# ESP32-S3.net
KiCad netlist of a schematic drawn in Altium Designer
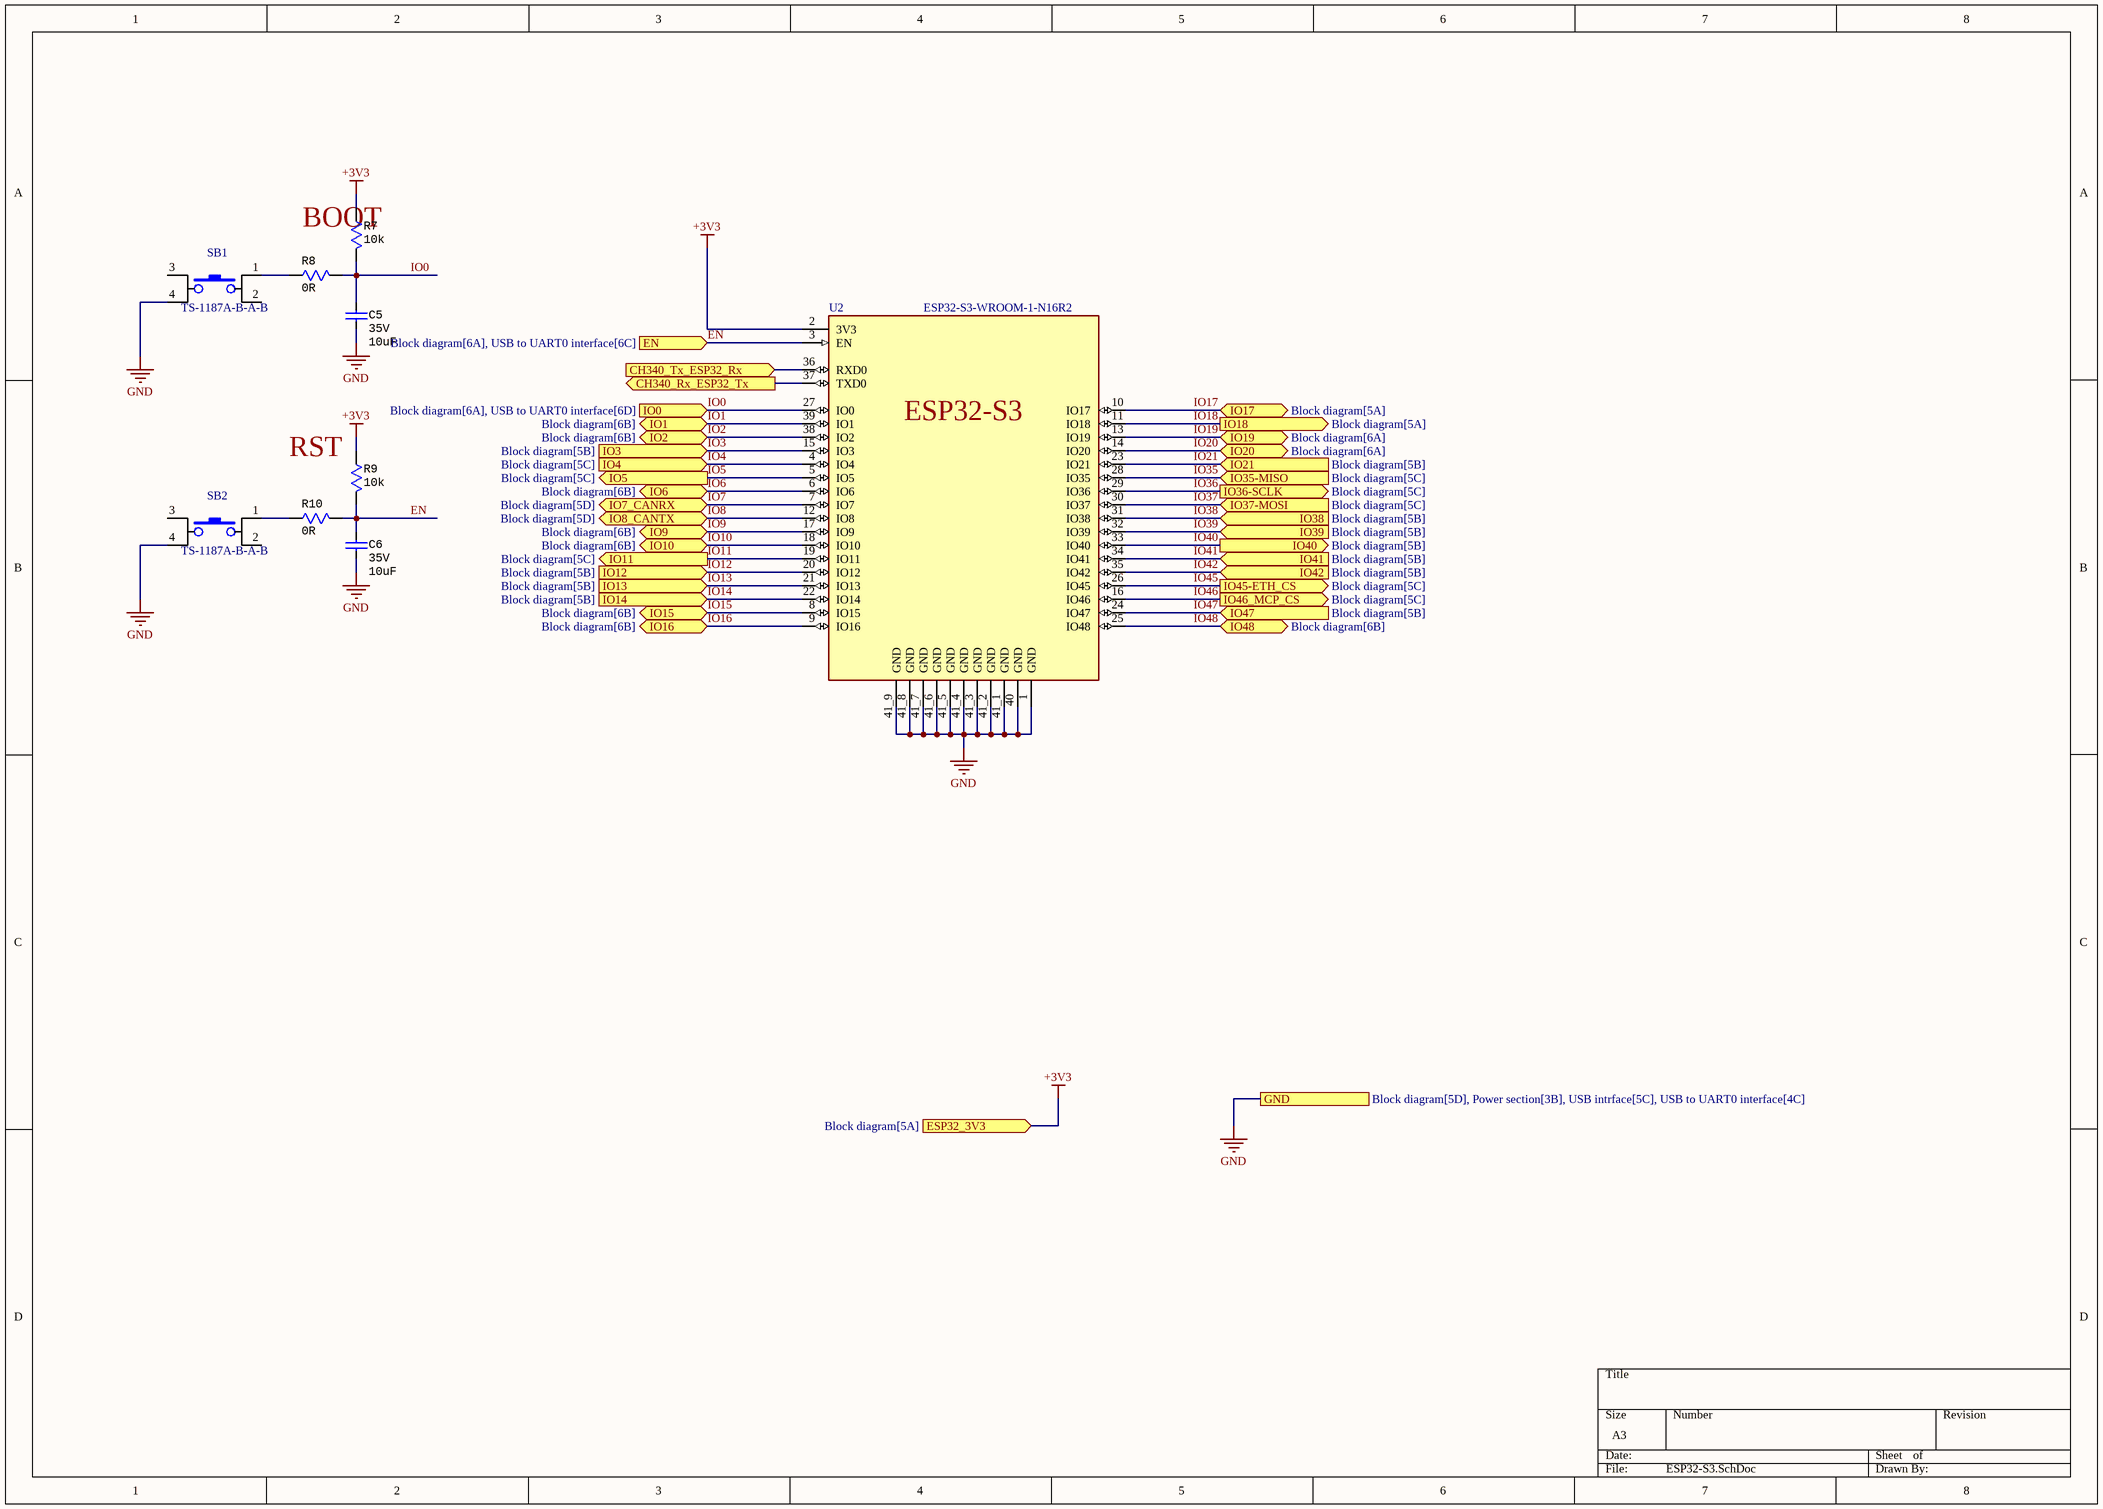
[diagram p0: ESP32-S3.SchDoc]

(export (version "E")
  (design (tool "Eeschema 10.0.6"))
  (components
    (comp (ref "C5")
      (value "10uF")
      (footprint "CAP Ceramic SMD 0603")
      (description "Cap Ceramic 10uF 35V X5R 20% Pad SMD 0603 85C T/R")
      (fields
        (field (name "MANUFACTURER") "Murata")
        (field (name "MANUFACTURER PART NUMBER") "GRM188R6YA106MA73D")
        (field (name "VOLTAGE") "35V")
      )
      (libsource (lib "Passive") (part "CAP 0603 10uF 35V"))
    )
    (comp (ref "C6")
      (value "10uF")
      (footprint "CAP Ceramic SMD 0603")
      (description "Cap Ceramic 10uF 35V X5R 20% Pad SMD 0603 85C T/R")
      (fields
        (field (name "MANUFACTURER") "Murata")
        (field (name "MANUFACTURER PART NUMBER") "GRM188R6YA106MA73D")
        (field (name "VOLTAGE") "35V")
      )
      (libsource (lib "Passive") (part "CAP 0603 10uF 35V"))
    )
    (comp (ref "R7")
      (value "10k")
      (footprint "RES SMD 0603")
      (description "Res Thick Film 0603 10K Ohm 1% 1/10W ±100ppm/°C Molded SMD Punched Carrier T/R")
      (fields
        (field (name "MANUFACTURER") "Panasonic")
        (field (name "MANUFACTURER PART NUMBER") "ERJ-3EKF1002V")
      )
      (libsource (lib "Passive") (part "RES 0603 10k 1%"))
    )
    (comp (ref "R8")
      (value "0R")
      (footprint "RES SMD 0603")
      (description "ERJ Series 0603 0 Ohm 0.05 W Jumper Surface Mount Thick Film Chip Resistor")
      (fields (field (name "TOLERANCE") "1%") (field (name "MANUFACTURER") "Panasonic"))
      (libsource (lib "Passive") (part "RES 0603 0R 1%"))
    )
    (comp (ref "R9")
      (value "10k")
      (footprint "RES SMD 0603")
      (description "Res Thick Film 0603 10K Ohm 1% 1/10W ±100ppm/°C Molded SMD Punched Carrier T/R")
      (fields
        (field (name "MANUFACTURER") "Panasonic")
        (field (name "MANUFACTURER PART NUMBER") "ERJ-3EKF1002V")
      )
      (libsource (lib "Passive") (part "RES 0603 10k 1%"))
    )
    (comp (ref "R10")
      (value "0R")
      (footprint "RES SMD 0603")
      (description "ERJ Series 0603 0 Ohm 0.05 W Jumper Surface Mount Thick Film Chip Resistor")
      (fields (field (name "TOLERANCE") "1%") (field (name "MANUFACTURER") "Panasonic"))
      (libsource (lib "Passive") (part "RES 0603 0R 1%"))
    )
    (comp (ref "SB1")
      (value "TS-1187A-B-A-B")
      (footprint "SW-SMD-4X4X1.5")
      (libsource (lib "Switches") (part "TS-1187A-B-A-B"))
    )
    (comp (ref "SB2")
      (value "TS-1187A-B-A-B")
      (footprint "SW-SMD-4X4X1.5")
      (libsource (lib "Switches") (part "TS-1187A-B-A-B"))
    )
    (comp (ref "U2")
      (value "ESP32-S3-WROOM-1-N16R2")
      (footprint "ESP32-S3-WROOM-1-N16R2")
      (description "WiFi-Modul 802.11/BT 2, 4-2, 5GHz 150Mb/s")
      (fields (field (name "MANUFACTURER") "Espressif Systems"))
      (libsource (lib "Miscellaneous MCU") (part "ESP32-S3-WROOM-1-N16R2"))
    )
  )
  (nets
    (net (code "1") (name "+3V3") (class "Default")
      (node (ref "R7") (pin "2") (pinfunction "2_2") (pintype "passive"))
      (node (ref "R9") (pin "2") (pinfunction "2_2") (pintype "passive"))
      (node (ref "U2") (pin "2") (pinfunction "3V3_2") (pintype "power_in"))
    )
    (net (code "2") (name "/CH340_Rx_ESP32_Tx") (class "Default")
      (node (ref "U2") (pin "37") (pinfunction "TXD0_37") (pintype "bidirectional"))
    )
    (net (code "3") (name "/CH340_Tx_ESP32_Rx") (class "Default")
      (node (ref "U2") (pin "36") (pinfunction "RXD0_36") (pintype "bidirectional"))
    )
    (net (code "4") (name "/EN") (class "Default")
      (node (ref "C6") (pin "2") (pinfunction "2_2") (pintype "passive"))
      (node (ref "R10") (pin "1") (pinfunction "1_1") (pintype "passive"))
      (node (ref "R9") (pin "1") (pinfunction "1_1") (pintype "passive"))
      (node (ref "U2") (pin "3") (pinfunction "EN_3") (pintype "input"))
    )
    (net (code "5") (name "/IO0") (class "Default")
      (node (ref "C5") (pin "2") (pinfunction "2_2") (pintype "passive"))
      (node (ref "R7") (pin "1") (pinfunction "1_1") (pintype "passive"))
      (node (ref "R8") (pin "1") (pinfunction "1_1") (pintype "passive"))
      (node (ref "U2") (pin "27") (pinfunction "IO0_27") (pintype "bidirectional"))
    )
    (net (code "6") (name "/IO1") (class "Default")
      (node (ref "U2") (pin "39") (pinfunction "IO1_39") (pintype "bidirectional"))
    )
    (net (code "7") (name "/IO2") (class "Default")
      (node (ref "U2") (pin "38") (pinfunction "IO2_38") (pintype "bidirectional"))
    )
    (net (code "8") (name "/IO3") (class "Default")
      (node (ref "U2") (pin "15") (pinfunction "IO3_15") (pintype "bidirectional"))
    )
    (net (code "9") (name "/IO4") (class "Default")
      (node (ref "U2") (pin "4") (pinfunction "IO4_4") (pintype "bidirectional"))
    )
    (net (code "10") (name "/IO5") (class "Default")
      (node (ref "U2") (pin "5") (pinfunction "IO5_5") (pintype "bidirectional"))
    )
    (net (code "11") (name "/IO6") (class "Default")
      (node (ref "U2") (pin "6") (pinfunction "IO6_6") (pintype "bidirectional"))
    )
    (net (code "12") (name "/IO7") (class "Default")
      (node (ref "U2") (pin "7") (pinfunction "IO7_7") (pintype "bidirectional"))
    )
    (net (code "13") (name "/IO8") (class "Default")
      (node (ref "U2") (pin "12") (pinfunction "IO8_12") (pintype "bidirectional"))
    )
    (net (code "14") (name "/IO9") (class "Default")
      (node (ref "U2") (pin "17") (pinfunction "IO9_17") (pintype "bidirectional"))
    )
    (net (code "15") (name "/IO10") (class "Default")
      (node (ref "U2") (pin "18") (pinfunction "IO10_18") (pintype "bidirectional"))
    )
    (net (code "16") (name "/IO11") (class "Default")
      (node (ref "U2") (pin "19") (pinfunction "IO11_19") (pintype "bidirectional"))
    )
    (net (code "17") (name "/IO12") (class "Default")
      (node (ref "U2") (pin "20") (pinfunction "IO12_20") (pintype "bidirectional"))
    )
    (net (code "18") (name "/IO13") (class "Default")
      (node (ref "U2") (pin "21") (pinfunction "IO13_21") (pintype "bidirectional"))
    )
    (net (code "19") (name "/IO14") (class "Default")
      (node (ref "U2") (pin "22") (pinfunction "IO14_22") (pintype "bidirectional"))
    )
    (net (code "20") (name "/IO15") (class "Default")
      (node (ref "U2") (pin "8") (pinfunction "IO15_8") (pintype "bidirectional"))
    )
    (net (code "21") (name "/IO16") (class "Default")
      (node (ref "U2") (pin "9") (pinfunction "IO16_9") (pintype "bidirectional"))
    )
    (net (code "22") (name "/IO17") (class "Default")
      (node (ref "U2") (pin "10") (pinfunction "IO17_10") (pintype "bidirectional"))
    )
    (net (code "23") (name "/IO18") (class "Default")
      (node (ref "U2") (pin "11") (pinfunction "IO18_11") (pintype "bidirectional"))
    )
    (net (code "24") (name "/IO19") (class "Default")
      (node (ref "U2") (pin "13") (pinfunction "IO19_13") (pintype "bidirectional"))
    )
    (net (code "25") (name "/IO20") (class "Default")
      (node (ref "U2") (pin "14") (pinfunction "IO20_14") (pintype "bidirectional"))
    )
    (net (code "26") (name "/IO21") (class "Default")
      (node (ref "U2") (pin "23") (pinfunction "IO21_23") (pintype "bidirectional"))
    )
    (net (code "27") (name "/IO35") (class "Default")
      (node (ref "U2") (pin "28") (pinfunction "IO35_28") (pintype "bidirectional"))
    )
    (net (code "28") (name "/IO36") (class "Default")
      (node (ref "U2") (pin "29") (pinfunction "IO36_29") (pintype "bidirectional"))
    )
    (net (code "29") (name "/IO37") (class "Default")
      (node (ref "U2") (pin "30") (pinfunction "IO37_30") (pintype "bidirectional"))
    )
    (net (code "30") (name "/IO38") (class "Default")
      (node (ref "U2") (pin "31") (pinfunction "IO38_31") (pintype "bidirectional"))
    )
    (net (code "31") (name "/IO39") (class "Default")
      (node (ref "U2") (pin "32") (pinfunction "IO39_32") (pintype "bidirectional"))
    )
    (net (code "32") (name "/IO40") (class "Default")
      (node (ref "U2") (pin "33") (pinfunction "IO40_33") (pintype "bidirectional"))
    )
    (net (code "33") (name "/IO41") (class "Default")
      (node (ref "U2") (pin "34") (pinfunction "IO41_34") (pintype "bidirectional"))
    )
    (net (code "34") (name "/IO42") (class "Default")
      (node (ref "U2") (pin "35") (pinfunction "IO42_35") (pintype "bidirectional"))
    )
    (net (code "35") (name "/IO45") (class "Default")
      (node (ref "U2") (pin "26") (pinfunction "IO45_26") (pintype "bidirectional"))
    )
    (net (code "36") (name "/IO46") (class "Default")
      (node (ref "U2") (pin "16") (pinfunction "IO46_16") (pintype "bidirectional"))
    )
    (net (code "37") (name "/IO47") (class "Default")
      (node (ref "U2") (pin "24") (pinfunction "IO47_24") (pintype "bidirectional"))
    )
    (net (code "38") (name "/IO48") (class "Default")
      (node (ref "U2") (pin "25") (pinfunction "IO48_25") (pintype "bidirectional"))
    )
    (net (code "39") (name "GND") (class "Default")
      (node (ref "C5") (pin "1") (pinfunction "1_1") (pintype "passive"))
      (node (ref "C6") (pin "1") (pinfunction "1_1") (pintype "passive"))
      (node (ref "SB1") (pin "4") (pinfunction "4_4") (pintype "passive"))
      (node (ref "SB2") (pin "4") (pinfunction "4_4") (pintype "passive"))
      (node (ref "U2") (pin "1") (pinfunction "GND_1") (pintype "power_in"))
      (node (ref "U2") (pin "40") (pinfunction "GND_40") (pintype "power_in"))
      (node (ref "U2") (pin "41_1") (pinfunction "GND_41_1") (pintype "power_in"))
      (node (ref "U2") (pin "41_2") (pinfunction "GND_41_2") (pintype "power_in"))
      (node (ref "U2") (pin "41_3") (pinfunction "GND_41_3") (pintype "power_in"))
      (node (ref "U2") (pin "41_4") (pinfunction "GND_41_4") (pintype "power_in"))
      (node (ref "U2") (pin "41_5") (pinfunction "GND_41_5") (pintype "power_in"))
      (node (ref "U2") (pin "41_6") (pinfunction "GND_41_6") (pintype "power_in"))
      (node (ref "U2") (pin "41_7") (pinfunction "GND_41_7") (pintype "power_in"))
      (node (ref "U2") (pin "41_8") (pinfunction "GND_41_8") (pintype "power_in"))
      (node (ref "U2") (pin "41_9") (pinfunction "GND_41_9") (pintype "power_in"))
    )
    (net (code "40") (name "Net-(R8-Pad2)") (class "Default")
      (node (ref "R8") (pin "2") (pinfunction "2_2") (pintype "passive"))
      (node (ref "SB1") (pin "1") (pinfunction "1_1") (pintype "passive"))
    )
    (net (code "41") (name "Net-(R10-Pad2)") (class "Default")
      (node (ref "R10") (pin "2") (pinfunction "2_2") (pintype "passive"))
      (node (ref "SB2") (pin "1") (pinfunction "1_1") (pintype "passive"))
    )
    (net (code "42") (name "unconnected-(SB1-Pad2)") (class "Default")
      (node (ref "SB1") (pin "2") (pinfunction "2_2") (pintype "passive"))
    )
    (net (code "43") (name "unconnected-(SB1-Pad3)") (class "Default")
      (node (ref "SB1") (pin "3") (pinfunction "3_3") (pintype "passive"))
    )
    (net (code "44") (name "unconnected-(SB2-Pad2)") (class "Default")
      (node (ref "SB2") (pin "2") (pinfunction "2_2") (pintype "passive"))
    )
    (net (code "45") (name "unconnected-(SB2-Pad3)") (class "Default")
      (node (ref "SB2") (pin "3") (pinfunction "3_3") (pintype "passive"))
    )
  )
)
